# DM1098OAKW_RIGHT_OV9282.net
KiCad netlist of a schematic drawn in Altium Designer
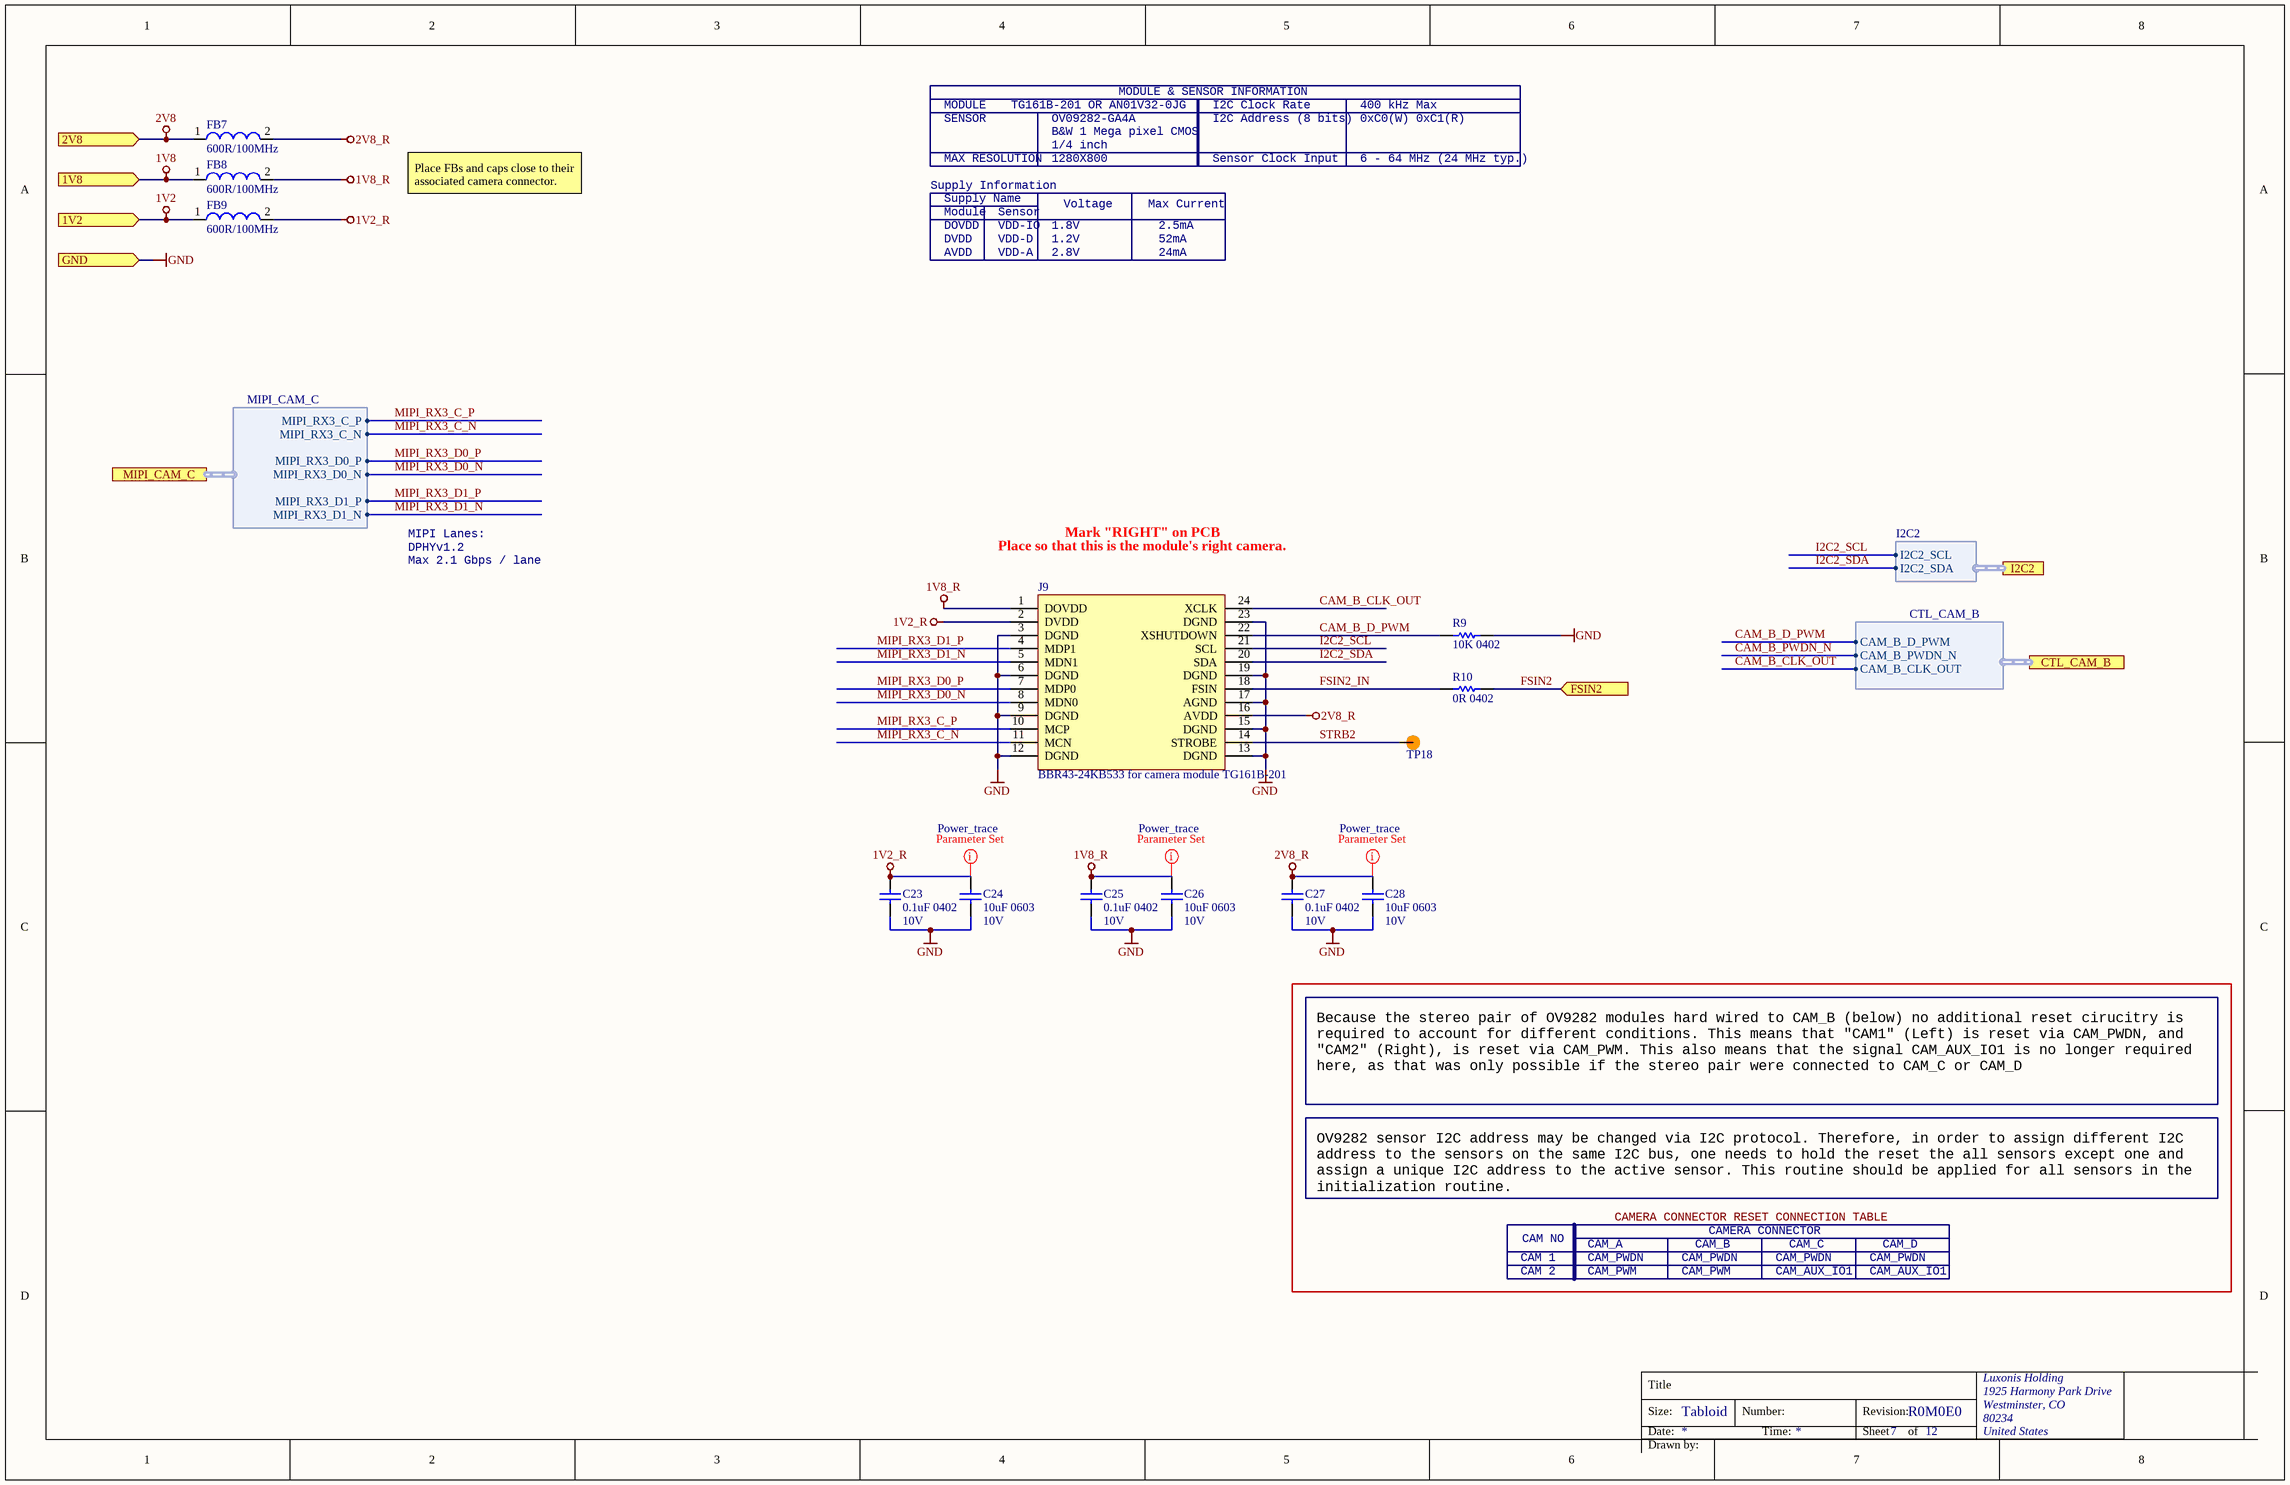
[diagram p0: DM1098OAKW_RIGHT_OV9282.SchDoc]

(export (version "E")
  (design (tool "Eeschema 10.0.6"))
  (components
    (comp (ref "C23")
      (value "0.1uF 0402")
      (footprint "CAP_Altium_Vault_Generic:CAPC0402(1005)70_L")
      (description "CAP CER 0.1UF 10V X7R 0402 5%")
      (fields (field (name "TOLERANCE") "5%") (field (name "VOLTAGE RATING") "10V"))
      (libsource (lib "LuxonisMaster") (part "GRM155R71A104JA01D"))
    )
    (comp (ref "C24")
      (value "10uF 0603")
      (footprint "CAP_Altium_Vault_Generic:CAPC0603(1608)100_L")
      (description "CAP CER 10UF 10V X5R 0603 20%")
      (fields (field (name "TOLERANCE") "20%") (field (name "VOLTAGE RATING") "10V"))
      (libsource (lib "LuxonisMaster") (part "GRM188R61A106ME69D"))
    )
    (comp (ref "C25")
      (value "0.1uF 0402")
      (footprint "CAP_Altium_Vault_Generic:CAPC0402(1005)70_L")
      (description "CAP CER 0.1UF 10V X7R 0402 5%")
      (fields (field (name "TOLERANCE") "5%") (field (name "VOLTAGE RATING") "10V"))
      (libsource (lib "LuxonisMaster") (part "GRM155R71A104JA01D"))
    )
    (comp (ref "C26")
      (value "10uF 0603")
      (footprint "CAP_Altium_Vault_Generic:CAPC0603(1608)100_L")
      (description "CAP CER 10UF 10V X5R 0603 20%")
      (fields (field (name "TOLERANCE") "20%") (field (name "VOLTAGE RATING") "10V"))
      (libsource (lib "LuxonisMaster") (part "GRM188R61A106ME69D"))
    )
    (comp (ref "C27")
      (value "0.1uF 0402")
      (footprint "CAP_Altium_Vault_Generic:CAPC0402(1005)70_L")
      (description "CAP CER 0.1UF 10V X7R 0402 5%")
      (fields (field (name "TOLERANCE") "5%") (field (name "VOLTAGE RATING") "10V"))
      (libsource (lib "LuxonisMaster") (part "GRM155R71A104JA01D"))
    )
    (comp (ref "C28")
      (value "10uF 0603")
      (footprint "CAP_Altium_Vault_Generic:CAPC0603(1608)100_L")
      (description "CAP CER 10UF 10V X5R 0603 20%")
      (fields (field (name "TOLERANCE") "20%") (field (name "VOLTAGE RATING") "10V"))
      (libsource (lib "LuxonisMaster") (part "GRM188R61A106ME69D"))
    )
    (comp (ref "FB7")
      (value "600R/100MHz")
      (footprint "LuxonisMaster:2508056017Y2")
      (description "FERRITE BEAD, 0.1OHM, 2A, 0805, 600R/100MHz")
      (fields (field (name "TOLERANCE") "25%"))
      (libsource (lib "LuxonisMaster") (part "2508056017Y2"))
    )
    (comp (ref "FB8")
      (value "600R/100MHz")
      (footprint "LuxonisMaster:2508056017Y2")
      (description "FERRITE BEAD, 0.1OHM, 2A, 0805, 600R/100MHz")
      (fields (field (name "TOLERANCE") "25%"))
      (libsource (lib "LuxonisMaster") (part "2508056017Y2"))
    )
    (comp (ref "FB9")
      (value "600R/100MHz")
      (footprint "LuxonisMaster:2508056017Y2")
      (description "FERRITE BEAD, 0.1OHM, 2A, 0805, 600R/100MHz")
      (fields (field (name "TOLERANCE") "25%"))
      (libsource (lib "LuxonisMaster") (part "2508056017Y2"))
    )
    (comp (ref "J9")
      (value "BBR43-24KB533 for camera module TG161B-201")
      (footprint "LuxonisMaster:TG161B-201")
      (description "CONN 24 way, 2 row board to board connector SMD")
      (libsource (lib "LuxonisMaster") (part "TG161B-201_Connector"))
    )
    (comp (ref "R9")
      (value "10K 0402")
      (footprint "RES_Altium_Vault_Generic:RESC0402(1005)_L")
      (fields (field (name "TOLERANCE") "1%"))
      (libsource (lib "LuxonisMaster") (part "RC0402FR-1310KL"))
    )
    (comp (ref "R10")
      (value "0R 0402")
      (footprint "RES_Altium_Vault_Generic:RESC0402(1005)_L")
      (description "RES SMD 0 OHM JUMPER 1/16W 0402")
      (fields (field (name "TOLERANCE") "5%"))
      (libsource (lib "LuxonisMaster") (part "CRCW04020000Z0ED"))
    )
    (comp (ref "TP18")
      (value "TP100_200_NS")
      (footprint "LuxonisMaster:TP100_200_NS")
      (libsource (lib "LuxonisMaster") (part "TEST_POINT"))
    )
  )
  (nets
    (net (code "4") (name "/CAM_B_CLK_OUT") (class "Default")
      (node (ref "J9") (pin "24") (pinfunction "XCLK_24") (pintype "passive"))
    )
    (net (code "5") (name "/CAM_B_D_PWM") (class "Default")
      (node (ref "J9") (pin "22") (pinfunction "XSHUTDOWN_22") (pintype "passive"))
      (node (ref "R9") (pin "1") (pinfunction "1_1") (pintype "passive"))
    )
    (net (code "7") (name "/FSIN2") (class "Default")
      (node (ref "R10") (pin "2") (pinfunction "2_2") (pintype "passive"))
    )
    (net (code "8") (name "/FSIN2_IN") (class "Default")
      (node (ref "J9") (pin "18") (pinfunction "FSIN_18") (pintype "passive"))
      (node (ref "R10") (pin "1") (pinfunction "1_1") (pintype "passive"))
    )
    (net (code "9") (name "/I2C2_SCL") (class "Default")
      (node (ref "J9") (pin "21") (pinfunction "SCL_21") (pintype "passive"))
    )
    (net (code "10") (name "/I2C2_SDA") (class "Default")
      (node (ref "J9") (pin "20") (pinfunction "SDA_20") (pintype "passive"))
    )
    (net (code "11") (name "/MIPI_RX3_C_N") (class "Default")
      (node (ref "J9") (pin "11") (pinfunction "MCN_11") (pintype "passive"))
    )
    (net (code "12") (name "/MIPI_RX3_C_P") (class "Default")
      (node (ref "J9") (pin "10") (pinfunction "MCP_10") (pintype "passive"))
    )
    (net (code "13") (name "/MIPI_RX3_D0_N") (class "Default")
      (node (ref "J9") (pin "8") (pinfunction "MDN0_8") (pintype "passive"))
    )
    (net (code "14") (name "/MIPI_RX3_D0_P") (class "Default")
      (node (ref "J9") (pin "7") (pinfunction "MDP0_7") (pintype "passive"))
    )
    (net (code "15") (name "/MIPI_RX3_D1_N") (class "Default")
      (node (ref "J9") (pin "5") (pinfunction "MDN1_5") (pintype "passive"))
    )
    (net (code "16") (name "/MIPI_RX3_D1_P") (class "Default")
      (node (ref "J9") (pin "4") (pinfunction "MDP1_4") (pintype "passive"))
    )
    (net (code "17") (name "/STRB2") (class "Default")
      (node (ref "J9") (pin "14") (pinfunction "STROBE_14") (pintype "passive"))
      (node (ref "TP18") (pin "1") (pintype "passive"))
    )
    (net (code "21") (name "1V2") (class "Default")
      (node (ref "FB9") (pin "1") (pinfunction "1_1") (pintype "passive"))
    )
    (net (code "22") (name "1V2_R") (class "Default")
      (node (ref "C23") (pin "2") (pinfunction "2_2") (pintype "passive"))
      (node (ref "C24") (pin "2") (pinfunction "2_2") (pintype "passive"))
      (node (ref "FB9") (pin "2") (pinfunction "2_2") (pintype "passive"))
      (node (ref "J9") (pin "2") (pinfunction "DVDD_2") (pintype "passive"))
    )
    (net (code "23") (name "1V8") (class "Default")
      (node (ref "FB8") (pin "1") (pinfunction "1_1") (pintype "passive"))
    )
    (net (code "24") (name "1V8_R") (class "Default")
      (node (ref "C25") (pin "2") (pinfunction "2_2") (pintype "passive"))
      (node (ref "C26") (pin "2") (pinfunction "2_2") (pintype "passive"))
      (node (ref "FB8") (pin "2") (pinfunction "2_2") (pintype "passive"))
      (node (ref "J9") (pin "1") (pinfunction "DOVDD_1") (pintype "passive"))
    )
    (net (code "25") (name "2V8") (class "Default")
      (node (ref "FB7") (pin "1") (pinfunction "1_1") (pintype "passive"))
    )
    (net (code "26") (name "2V8_R") (class "Default")
      (node (ref "C27") (pin "2") (pinfunction "2_2") (pintype "passive"))
      (node (ref "C28") (pin "2") (pinfunction "2_2") (pintype "passive"))
      (node (ref "FB7") (pin "2") (pinfunction "2_2") (pintype "passive"))
      (node (ref "J9") (pin "16") (pinfunction "AVDD_16") (pintype "passive"))
    )
    (net (code "27") (name "GND") (class "Default")
      (node (ref "C23") (pin "1") (pinfunction "1_1") (pintype "passive"))
      (node (ref "C24") (pin "1") (pinfunction "1_1") (pintype "passive"))
      (node (ref "C25") (pin "1") (pinfunction "1_1") (pintype "passive"))
      (node (ref "C26") (pin "1") (pinfunction "1_1") (pintype "passive"))
      (node (ref "C27") (pin "1") (pinfunction "1_1") (pintype "passive"))
      (node (ref "C28") (pin "1") (pinfunction "1_1") (pintype "passive"))
      (node (ref "J9") (pin "12") (pinfunction "DGND_12") (pintype "passive"))
      (node (ref "J9") (pin "13") (pinfunction "DGND_13") (pintype "passive"))
      (node (ref "J9") (pin "15") (pinfunction "DGND_15") (pintype "passive"))
      (node (ref "J9") (pin "17") (pinfunction "AGND_17") (pintype "passive"))
      (node (ref "J9") (pin "19") (pinfunction "DGND_19") (pintype "passive"))
      (node (ref "J9") (pin "23") (pinfunction "DGND_23") (pintype "passive"))
      (node (ref "J9") (pin "3") (pinfunction "DGND_3") (pintype "passive"))
      (node (ref "J9") (pin "6") (pinfunction "DGND_6") (pintype "passive"))
      (node (ref "J9") (pin "9") (pinfunction "DGND_9") (pintype "passive"))
      (node (ref "R9") (pin "2") (pinfunction "2_2") (pintype "passive"))
    )
  )
)
